# Stat_LED_Driver.net
KiCad netlist of a schematic drawn in Altium Designer
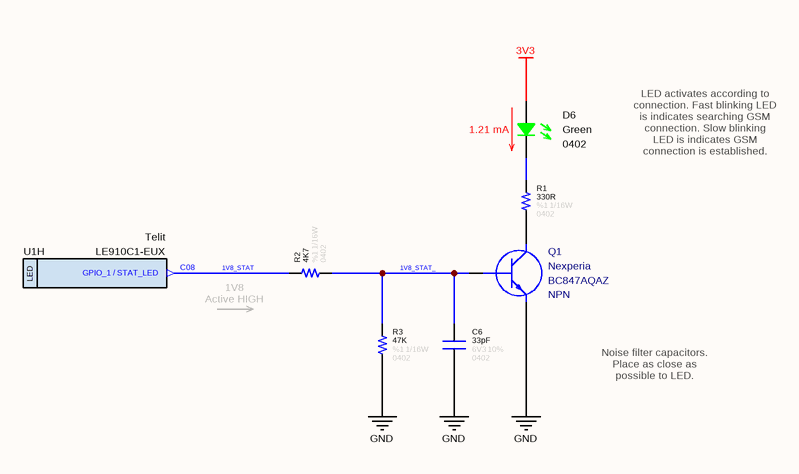
[diagram p0: Stat_LED_Driver.SchDoc]

(export (version "E")
  (design (tool "Eeschema 10.0.6"))
  (components
    (comp (ref "C6")
      (value "33pF")
      (footprint "CAPACITOR_0402")
      (description "Capacitor - 33pF [0402] (Ceramic)")
      (fields
        (field (name "MANUFACTURER PART NUMBER") "C0402C330J9RACAUTO")
        (field (name "TOLERANCE") "10%")
        (field (name "CASE") "0402")
        (field (name "VOLTAGE") "6V3")
      )
      (libsource (lib "P101DA_Library") (part "Capacitor - 33pF [0402-6V3]"))
    )
    (comp (ref "D6")
      (value "SMD LED (Green)")
      (footprint "LED_0402")
      (description "Standard LEDs - SMD MINI-MOLD ULTRA COMPACT GREEN")
      (fields
        (field (name "MANUFACTURER PART NUMBER") "SML-P12MTT86R")
        (field (name "CASE") "0402")
        (field (name "COLOR") "Green")
      )
      (libsource (lib "P101DA_Library") (part "Diode - LED (0402-Green)"))
    )
    (comp (ref "Q1")
      (value "BC847AQAZ")
      (footprint "SOT1215")
      (description "Bipolar NPN Transistors")
      (fields
        (field (name "MANUFACTURER NAME") "Nexperia")
        (field (name "MANUFACTURER PART NUMBER") "BC847AQAZ")
        (field (name "POLARITY") "NPN")
      )
      (libsource (lib "P101DA_Library") (part "Transistor - BC847"))
    )
    (comp (ref "R1")
      (value "330R")
      (footprint "RESISTOR_0402")
      (description "Thick Film Resistors - SMD 1/16 W 330 Ohm 1%")
      (fields
        (field (name "MANUFACTURER PART NUMBER") "CRCW0402330RFKED")
        (field (name "CASE") "0402")
        (field (name "TOLERANCE") "%1")
        (field (name "POWER") "1/16W")
        (field (name "Comment") "330R - 0402 - %1 - 1/16W")
      )
      (libsource (lib "P101DA_Library") (part "Resistor - 330R [0402]"))
    )
    (comp (ref "R2")
      (value "4K7")
      (footprint "RESISTOR_0402")
      (description "Thick Film Resistors - SMD 1/16 W 4.7 KOhm 1%")
      (fields
        (field (name "MANUFACTURER PART NUMBER") "CRCW04024K70FKED")
        (field (name "TOLERANCE") "%1")
        (field (name "CASE") "0402")
        (field (name "POWER") "1/16W")
        (field (name "Comment") "4K7 - 0402 - %1 - 1/16W")
      )
      (libsource (lib "P101DA_Library") (part "Resistor - 4K7 [0402]"))
    )
    (comp (ref "R3")
      (value "47K")
      (footprint "RESISTOR_0402")
      (description "Thick Film Resistors - SMD 1/16 W 47 KOhm 1%")
      (fields
        (field (name "MANUFACTURER PART NUMBER") "CRCW040247K0FKED")
        (field (name "TOLERANCE") "%1")
        (field (name "CASE") "0402")
        (field (name "POWER") "1/16W")
        (field (name "Comment") "47K - 0402 - %1 - 1/16W")
      )
      (libsource (lib "P101DA_Library") (part "Resistor - 47K [0402]"))
    )
    (comp (ref "U1")
      (value "LE910C1-EUX LTE GSM Module")
      (footprint "LE910 GSM Modem")
      (description "Telit LE910C1-EUX LTE/2G GSM Module")
      (fields
        (field (name "MANUFACTURER PART NUMBER") "LE910C1-EUX")
        (field (name "MANUFACTURER NAME") "Telit")
      )
      (libsource (lib "Akkoyun") (part "IC - LE910C1-EUX"))
    )
  )
  (nets
    (net (code "1") (name "/1V8_STAT") (class "Default")
      (node (ref "R2") (pin "2") (pinfunction "2_2") (pintype "passive"))
      (node (ref "U1") (pin "C08") (pinfunction "GPIO_1_/_STAT_LED_C08") (pintype "output"))
    )
    (net (code "2") (name "/1V8_STAT_") (class "Default")
      (node (ref "C6") (pin "2") (pinfunction "2_2") (pintype "passive"))
      (node (ref "Q1") (pin "1") (pinfunction "B_1") (pintype "passive"))
      (node (ref "R2") (pin "1") (pinfunction "1_1") (pintype "passive"))
      (node (ref "R3") (pin "2") (pinfunction "2_2") (pintype "passive"))
    )
    (net (code "3") (name "3V3") (class "Default")
      (node (ref "D6") (pin "2") (pinfunction "2_2") (pintype "passive"))
    )
    (net (code "4") (name "GND") (class "Default")
      (node (ref "C6") (pin "1") (pinfunction "1_1") (pintype "passive"))
      (node (ref "Q1") (pin "2") (pinfunction "E_2") (pintype "passive"))
      (node (ref "R3") (pin "1") (pinfunction "1_1") (pintype "passive"))
    )
    (net (code "5") (name "Net-(D6-Pad1)") (class "Default")
      (node (ref "D6") (pin "1") (pinfunction "1_1") (pintype "passive"))
      (node (ref "R1") (pin "2") (pinfunction "2_2") (pintype "passive"))
    )
    (net (code "6") (name "Net-(Q1-C)") (class "Default")
      (node (ref "Q1") (pin "3") (pinfunction "C_3") (pintype "passive"))
      (node (ref "R1") (pin "1") (pinfunction "1_1") (pintype "passive"))
    )
  )
)
